# led-cc-driver-mk-2_1.net
KiCad netlist of a schematic drawn in EAGLE
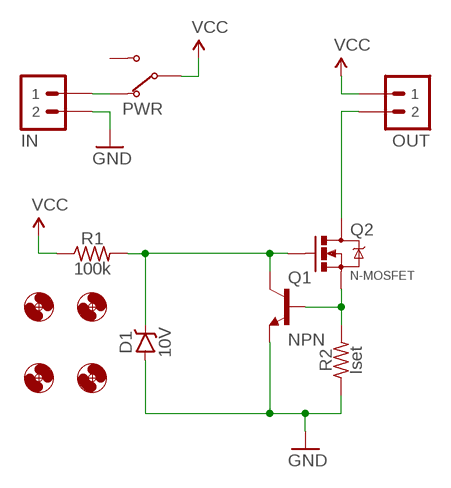
[diagram p0: schematic, sheet 1]

(export (version "E")
  (design (tool "Eeschema 10.0.6"))
  (components
    (comp (ref "D1")
      (value "10V")
      (footprint "eagle-import:DIODE-ZENNER-7.62MM")
      (libsource (lib "eagle-import") (part "DIODE-ZENER7.62MM-PTH"))
    )
    (comp (ref "H1")
      (value "HOLE#2")
      (footprint "eagle-import:HOLE-#2")
      (libsource (lib "eagle-import") (part "HOLE#2"))
    )
    (comp (ref "H2")
      (value "HOLE#2")
      (footprint "eagle-import:HOLE-#2")
      (libsource (lib "eagle-import") (part "HOLE#2"))
    )
    (comp (ref "H3")
      (value "HOLE#2")
      (footprint "eagle-import:HOLE-#2")
      (libsource (lib "eagle-import") (part "HOLE#2"))
    )
    (comp (ref "H4")
      (value "HOLE#2")
      (footprint "eagle-import:HOLE-#2")
      (libsource (lib "eagle-import") (part "HOLE#2"))
    )
    (comp (ref "IN")
      (value "M02JST-PTH-RA-SMALLPADS")
      (footprint "eagle-import:JST-2-PH-RA-PTH-SMALLPADS")
      (libsource (lib "eagle-import") (part "M02JST-PTH-RA-SMALLPADS"))
    )
    (comp (ref "OUT")
      (value "M02JST-PTH-RA-SMALLPADS")
      (footprint "eagle-import:JST-2-PH-RA-PTH-SMALLPADS")
      (libsource (lib "eagle-import") (part "M02JST-PTH-RA-SMALLPADS"))
    )
    (comp (ref "PWR")
      (value "SWITCH-SPDTPTH-VERT-2.54MM")
      (footprint "eagle-import:SWITCH-SPDT")
      (libsource (lib "eagle-import") (part "SWITCH-SPDTPTH-VERT-2.54MM"))
    )
    (comp (ref "Q1")
      (value "NPN")
      (footprint "eagle-import:TO-92-AMMO")
      (libsource (lib "eagle-import") (part "TRANSISTOR_NPNTO-92-AMMO-CBE"))
    )
    (comp (ref "Q2")
      (value "N-MOSFET")
      (footprint "eagle-import:TO220-THERMPAD")
      (libsource (lib "eagle-import") (part "MOSFET-NCHANNELTO-220"))
    )
    (comp (ref "R1")
      (value "100k")
      (footprint "eagle-import:RESISTOR-AXIAL-PTH-6.35MM")
      (libsource (lib "eagle-import") (part "RESISTORPTH-AXIAL-6.35MM"))
    )
    (comp (ref "R2")
      (value "Iset")
      (footprint "eagle-import:RESISTOR-AXIAL-PTH-10.16MM")
      (libsource (lib "eagle-import") (part "RESISTORPTH-AXIAL-10.16MM"))
    )
  )
  (nets
    (net (code "1") (name "GND") (class "Default")
      (node (ref "D1") (pin "A") (pinfunction "A_A") (pintype "passive"))
      (node (ref "IN") (pin "2") (pinfunction "2_2") (pintype "passive"))
      (node (ref "Q1") (pin "3") (pinfunction "E_3") (pintype "passive"))
      (node (ref "R2") (pin "P$1") (pinfunction "1_P$1") (pintype "passive"))
    )
    (net (code "2") (name "Net-(D1-C)") (class "Default")
      (node (ref "D1") (pin "K") (pinfunction "C_K") (pintype "passive"))
      (node (ref "Q1") (pin "1") (pinfunction "C_1") (pintype "passive"))
      (node (ref "Q2") (pin "1") (pinfunction "G_1") (pintype "passive"))
      (node (ref "R1") (pin "P$2") (pinfunction "2_P$2") (pintype "passive"))
    )
    (net (code "3") (name "Net-(OUT-Pad2)") (class "Default")
      (node (ref "OUT") (pin "2") (pinfunction "2_2") (pintype "passive"))
      (node (ref "Q2") (pin "2@1") (pinfunction "D_2@1") (pintype "passive"))
      (node (ref "Q2") (pin "2@2") (pinfunction "D_2@2") (pintype "passive"))
    )
    (net (code "4") (name "Net-(PWR-NC)") (class "Default")
      (node (ref "IN") (pin "1") (pinfunction "1_1") (pintype "passive"))
      (node (ref "PWR") (pin "1") (pinfunction "NC_1") (pintype "passive"))
    )
    (net (code "5") (name "Net-(Q1-B)") (class "Default")
      (node (ref "Q1") (pin "2") (pinfunction "B_2") (pintype "passive"))
      (node (ref "Q2") (pin "3") (pinfunction "S_3") (pintype "passive"))
      (node (ref "R2") (pin "P$2") (pinfunction "2_P$2") (pintype "passive"))
    )
    (net (code "6") (name "VCC") (class "Default")
      (node (ref "OUT") (pin "1") (pinfunction "1_1") (pintype "passive"))
      (node (ref "PWR") (pin "2") (pinfunction "COM_2") (pintype "passive"))
      (node (ref "R1") (pin "P$1") (pinfunction "1_P$1") (pintype "passive"))
    )
    (net (code "7") (name "unconnected-(PWR-NO-Pad3)") (class "Default")
      (node (ref "PWR") (pin "3") (pinfunction "NO_3") (pintype "passive"))
    )
  )
)
